# DDS_Module_r2.net
KiCad netlist of a schematic drawn in EAGLE
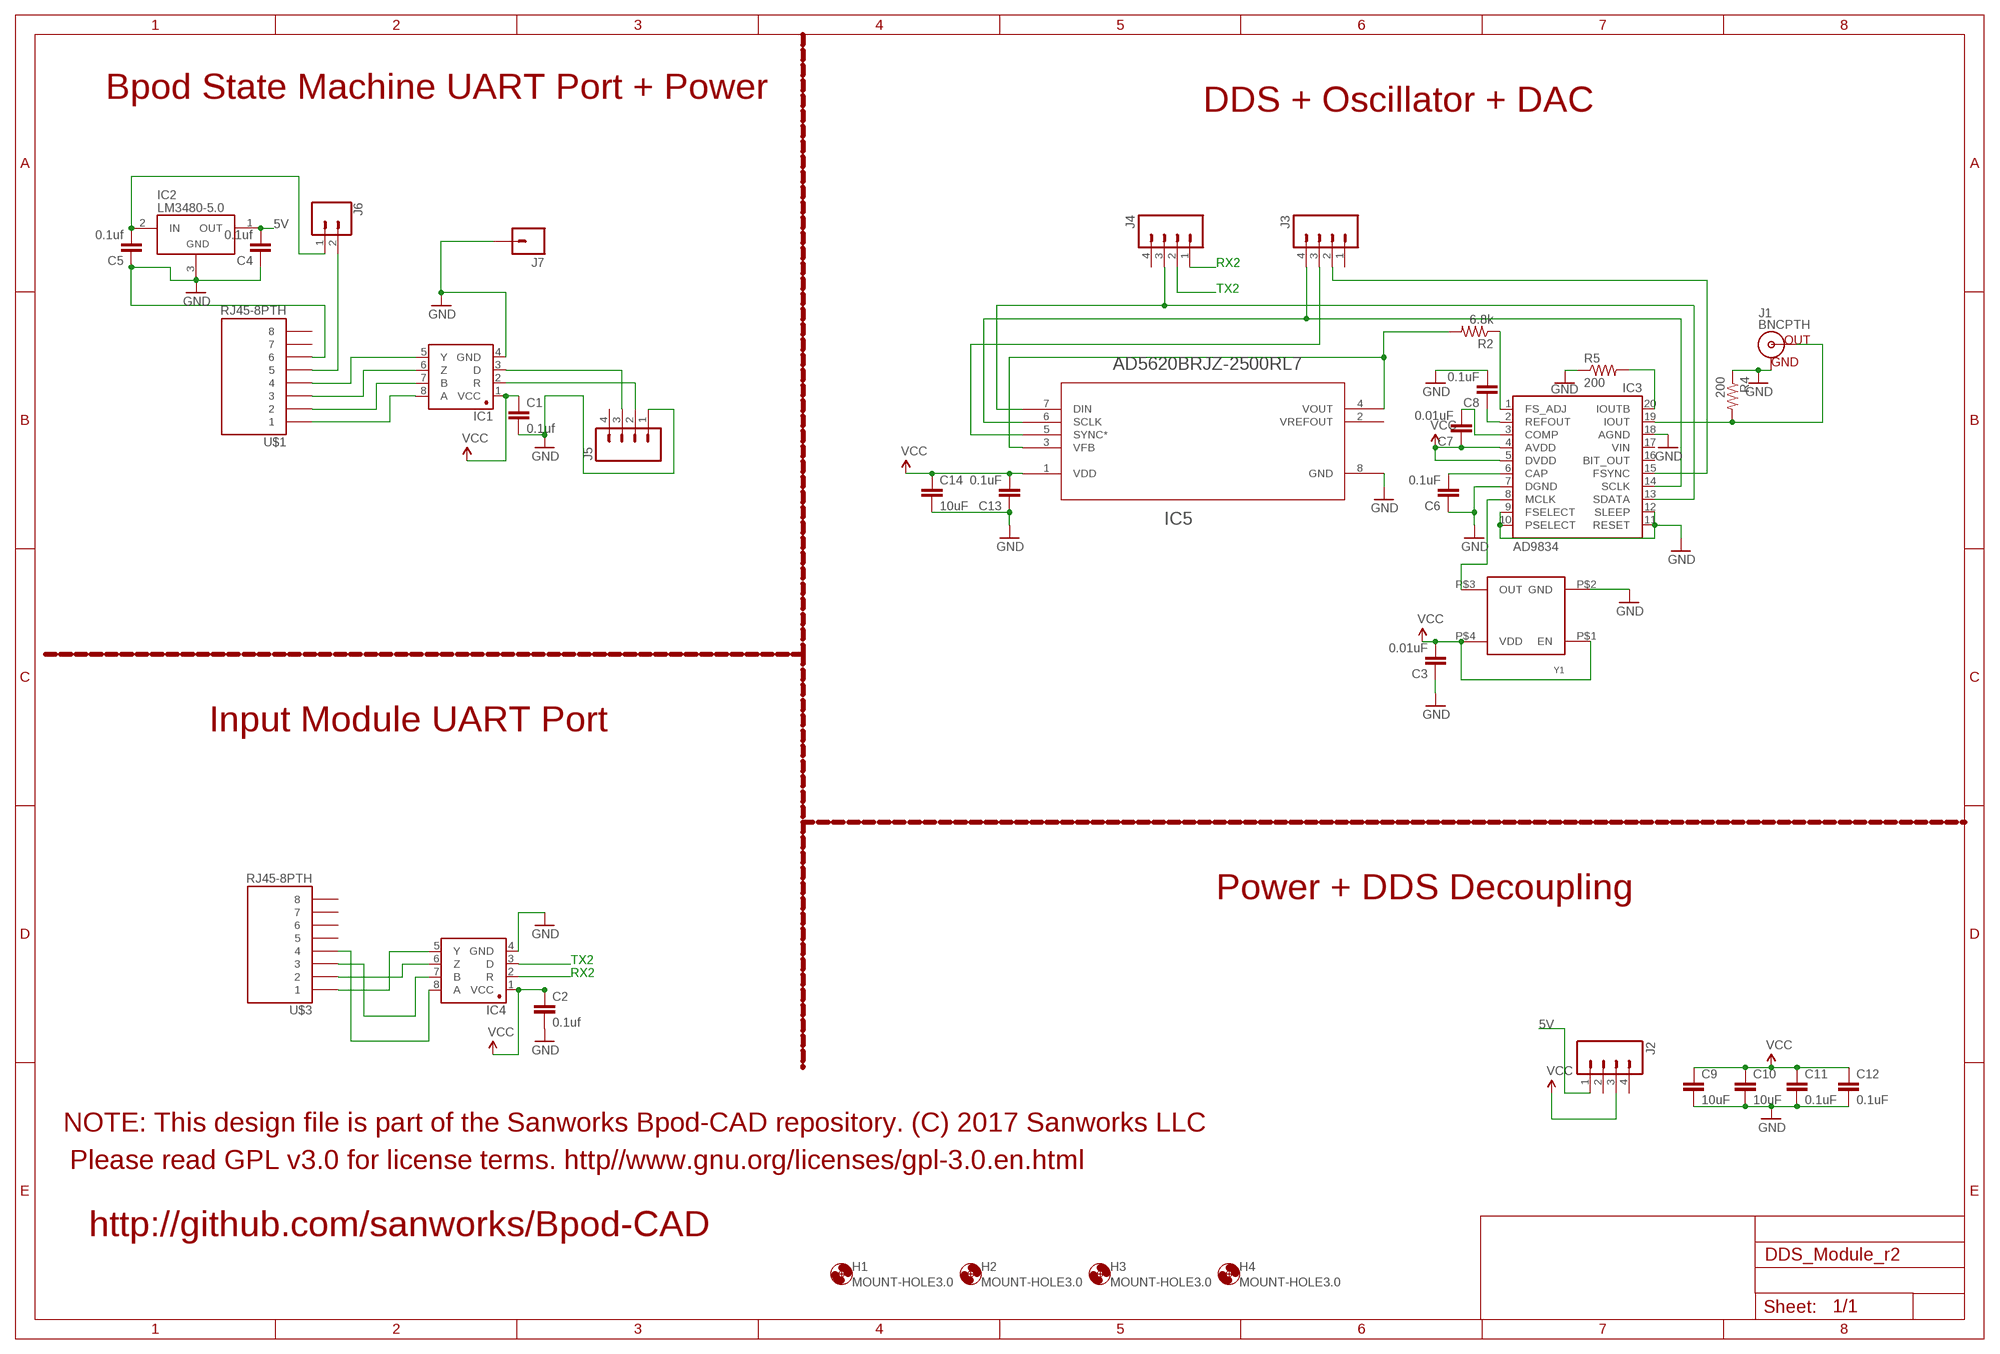
[diagram p0: schematic, sheet 1]

(export (version "E")
  (design (tool "Eeschema 10.0.6"))
  (components
    (comp (ref "C1")
      (value "0.1uf")
      (footprint "eagle-import:1206@1")
      (libsource (lib "eagle-import") (part "CAP1206"))
    )
    (comp (ref "C2")
      (value "0.1uf")
      (footprint "eagle-import:1206@1")
      (libsource (lib "eagle-import") (part "CAP1206"))
    )
    (comp (ref "C3")
      (value "0.01uF")
      (footprint "eagle-import:0805")
      (libsource (lib "eagle-import") (part "10UF-0805-10V-10%"))
    )
    (comp (ref "C4")
      (value "0.1uf")
      (footprint "eagle-import:1206@1")
      (libsource (lib "eagle-import") (part "CAP1206"))
    )
    (comp (ref "C5")
      (value "0.1uf")
      (footprint "eagle-import:1206@1")
      (libsource (lib "eagle-import") (part "CAP1206"))
    )
    (comp (ref "C6")
      (value "0.1uF")
      (footprint "eagle-import:0805")
      (libsource (lib "eagle-import") (part "10UF-0805-10V-10%"))
    )
    (comp (ref "C7")
      (value "0.01uF")
      (footprint "eagle-import:0805")
      (libsource (lib "eagle-import") (part "10UF-0805-10V-10%"))
    )
    (comp (ref "C8")
      (value "0.1uF")
      (footprint "eagle-import:0805")
      (libsource (lib "eagle-import") (part "10UF-0805-10V-10%"))
    )
    (comp (ref "C9")
      (value "10uF")
      (footprint "eagle-import:0805")
      (libsource (lib "eagle-import") (part "10UF-0805-10V-10%"))
    )
    (comp (ref "C10")
      (value "10uF")
      (footprint "eagle-import:0805")
      (libsource (lib "eagle-import") (part "10UF-0805-10V-10%"))
    )
    (comp (ref "C11")
      (value "0.1uF")
      (footprint "eagle-import:0805")
      (libsource (lib "eagle-import") (part "10UF-0805-10V-10%"))
    )
    (comp (ref "C12")
      (value "0.1uF")
      (footprint "eagle-import:0805")
      (libsource (lib "eagle-import") (part "10UF-0805-10V-10%"))
    )
    (comp (ref "C13")
      (value "0.1uF")
      (footprint "eagle-import:0805")
      (libsource (lib "eagle-import") (part "10UF-0805-10V-10%"))
    )
    (comp (ref "C14")
      (value "10uF")
      (footprint "eagle-import:0805")
      (libsource (lib "eagle-import") (part "10UF-0805-10V-10%"))
    )
    (comp (ref "H1")
      (value "MOUNT-HOLE3.0")
      (footprint "eagle-import:3,0")
      (libsource (lib "eagle-import") (part "MOUNT-HOLE3.0"))
    )
    (comp (ref "H2")
      (value "MOUNT-HOLE3.0")
      (footprint "eagle-import:3,0")
      (libsource (lib "eagle-import") (part "MOUNT-HOLE3.0"))
    )
    (comp (ref "H3")
      (value "MOUNT-HOLE3.0")
      (footprint "eagle-import:3,0")
      (libsource (lib "eagle-import") (part "MOUNT-HOLE3.0"))
    )
    (comp (ref "H4")
      (value "MOUNT-HOLE3.0")
      (footprint "eagle-import:3,0")
      (libsource (lib "eagle-import") (part "MOUNT-HOLE3.0"))
    )
    (comp (ref "IC1")
      (value "SN65HVD31DR")
      (footprint "eagle-import:SO08")
      (libsource (lib "eagle-import") (part "SN65HVD31DR"))
    )
    (comp (ref "IC2")
      (value "LM3480-5.0")
      (footprint "eagle-import:SOT-23-3")
      (libsource (lib "eagle-import") (part "LM3480-5.0"))
    )
    (comp (ref "IC3")
      (value "AD9834")
      (footprint "eagle-import:TSSOP20")
      (libsource (lib "eagle-import") (part "AD9834"))
    )
    (comp (ref "IC4")
      (value "SN65HVD31DR")
      (footprint "eagle-import:SO08")
      (libsource (lib "eagle-import") (part "SN65HVD31DR"))
    )
    (comp (ref "IC5")
      (value "AD5620BRJZ-2500RL7")
      (footprint "eagle-import:RJ_8")
      (fields (field (name "MANUFACTURER_PART_NUMBER") "AD5620BRJZ2500RL7"))
      (libsource (lib "eagle-import") (part "AD5620BRJZ-2500RL7"))
    )
    (comp (ref "J1")
      (value "BNCPTH")
      (footprint "eagle-import:BNC")
      (libsource (lib "eagle-import") (part "BNCPTH"))
    )
    (comp (ref "J2")
      (value "M04PTH")
      (footprint "eagle-import:1X04")
      (libsource (lib "eagle-import") (part "M04PTH"))
    )
    (comp (ref "J3")
      (value "M04PTH")
      (footprint "eagle-import:1X04")
      (libsource (lib "eagle-import") (part "M04PTH"))
    )
    (comp (ref "J4")
      (value "M04PTH")
      (footprint "eagle-import:1X04")
      (libsource (lib "eagle-import") (part "M04PTH"))
    )
    (comp (ref "J5")
      (value "M04PTH")
      (footprint "eagle-import:1X04")
      (libsource (lib "eagle-import") (part "M04PTH"))
    )
    (comp (ref "J6")
      (value "CONN_02")
      (footprint "eagle-import:1X02")
      (libsource (lib "eagle-import") (part "CONN_02"))
    )
    (comp (ref "J7")
      (value "M01PTH")
      (footprint "eagle-import:1X01")
      (libsource (lib "eagle-import") (part "M01PTH"))
    )
    (comp (ref "R2")
      (value "6.8k")
      (footprint "eagle-import:R0805")
      (libsource (lib "eagle-import") (part "R-US_R0805"))
    )
    (comp (ref "R4")
      (value "200")
      (footprint "eagle-import:R0805")
      (libsource (lib "eagle-import") (part "R-US_R0805"))
    )
    (comp (ref "R5")
      (value "200")
      (footprint "eagle-import:R0805")
      (libsource (lib "eagle-import") (part "R-US_R0805"))
    )
    (comp (ref "U$1")
      (value "RJ45-8PTH")
      (footprint "eagle-import:RJ45-8")
      (libsource (lib "eagle-import") (part "RJ45-8PTH"))
    )
    (comp (ref "U$3")
      (value "RJ45-8PTH")
      (footprint "eagle-import:RJ45-8")
      (libsource (lib "eagle-import") (part "RJ45-8PTH"))
    )
    (comp (ref "Y1")
      (value "ASE10MHZ")
      (footprint "eagle-import:ASE10MHZ")
      (libsource (lib "eagle-import") (part "ASE10MHZ"))
    )
  )
  (nets
    (net (code "1") (name "/5V") (class "Default")
      (node (ref "C4") (pin "2") (pinfunction "2_2") (pintype "passive"))
      (node (ref "IC2") (pin "1") (pinfunction "OUT_1") (pintype "power_in"))
      (node (ref "J2") (pin "1") (pinfunction "1_1") (pintype "passive"))
    )
    (net (code "2") (name "/RX2") (class "Default")
      (node (ref "IC4") (pin "2") (pinfunction "R_2") (pintype "bidirectional"))
      (node (ref "J4") (pin "1") (pinfunction "1_1") (pintype "passive"))
    )
    (net (code "3") (name "/TX2") (class "Default")
      (node (ref "IC4") (pin "3") (pinfunction "D_3") (pintype "bidirectional"))
      (node (ref "J4") (pin "2") (pinfunction "2_2") (pintype "passive"))
    )
    (net (code "4") (name "GND") (class "Default")
      (node (ref "C1") (pin "2") (pinfunction "2_2") (pintype "passive"))
      (node (ref "C10") (pin "2") (pinfunction "2_2") (pintype "passive"))
      (node (ref "C11") (pin "2") (pinfunction "2_2") (pintype "passive"))
      (node (ref "C12") (pin "2") (pinfunction "2_2") (pintype "passive"))
      (node (ref "C13") (pin "1") (pinfunction "1_1") (pintype "passive"))
      (node (ref "C14") (pin "2") (pinfunction "2_2") (pintype "passive"))
      (node (ref "C2") (pin "2") (pinfunction "2_2") (pintype "passive"))
      (node (ref "C3") (pin "1") (pinfunction "1_1") (pintype "passive"))
      (node (ref "C4") (pin "1") (pinfunction "1_1") (pintype "passive"))
      (node (ref "C5") (pin "1") (pinfunction "1_1") (pintype "passive"))
      (node (ref "C6") (pin "1") (pinfunction "1_1") (pintype "passive"))
      (node (ref "C8") (pin "2") (pinfunction "2_2") (pintype "passive"))
      (node (ref "C9") (pin "2") (pinfunction "2_2") (pintype "passive"))
      (node (ref "IC1") (pin "4") (pinfunction "GND_4") (pintype "bidirectional"))
      (node (ref "IC2") (pin "3") (pinfunction "GND_3") (pintype "power_in"))
      (node (ref "IC3") (pin "10") (pinfunction "PSELECT_10") (pintype "bidirectional"))
      (node (ref "IC3") (pin "11") (pinfunction "RESET_11") (pintype "bidirectional"))
      (node (ref "IC3") (pin "12") (pinfunction "SLEEP_12") (pintype "bidirectional"))
      (node (ref "IC3") (pin "18") (pinfunction "AGND_18") (pintype "bidirectional"))
      (node (ref "IC3") (pin "7") (pinfunction "DGND_7") (pintype "bidirectional"))
      (node (ref "IC3") (pin "9") (pinfunction "FSELECT_9") (pintype "bidirectional"))
      (node (ref "IC4") (pin "4") (pinfunction "GND_4") (pintype "bidirectional"))
      (node (ref "IC5") (pin "8") (pinfunction "GND_8") (pintype "passive"))
      (node (ref "J1") (pin "GND") (pinfunction "GND_GND") (pintype "bidirectional"))
      (node (ref "J5") (pin "1") (pinfunction "1_1") (pintype "passive"))
      (node (ref "J7") (pin "1") (pinfunction "1_1") (pintype "passive"))
      (node (ref "R4") (pin "1") (pinfunction "1_1") (pintype "passive"))
      (node (ref "R5") (pin "1") (pinfunction "1_1") (pintype "passive"))
      (node (ref "U$1") (pin "6") (pinfunction "6_6") (pintype "bidirectional"))
      (node (ref "Y1") (pin "P$2") (pinfunction "GND_P$2") (pintype "bidirectional"))
    )
    (net (code "5") (name "Net-(IC1-A)") (class "Default")
      (node (ref "IC1") (pin "8") (pinfunction "A_8") (pintype "bidirectional"))
      (node (ref "U$1") (pin "1") (pinfunction "1_1") (pintype "bidirectional"))
    )
    (net (code "6") (name "Net-(IC1-B)") (class "Default")
      (node (ref "IC1") (pin "7") (pinfunction "B_7") (pintype "bidirectional"))
      (node (ref "U$1") (pin "2") (pinfunction "2_2") (pintype "bidirectional"))
    )
    (net (code "7") (name "Net-(IC1-D)") (class "Default")
      (node (ref "IC1") (pin "3") (pinfunction "D_3") (pintype "bidirectional"))
      (node (ref "J5") (pin "3") (pinfunction "3_3") (pintype "passive"))
    )
    (net (code "8") (name "Net-(IC1-R)") (class "Default")
      (node (ref "IC1") (pin "2") (pinfunction "R_2") (pintype "bidirectional"))
      (node (ref "J5") (pin "2") (pinfunction "2_2") (pintype "passive"))
    )
    (net (code "9") (name "Net-(IC1-Y)") (class "Default")
      (node (ref "IC1") (pin "5") (pinfunction "Y_5") (pintype "bidirectional"))
      (node (ref "U$1") (pin "4") (pinfunction "4_4") (pintype "bidirectional"))
    )
    (net (code "10") (name "Net-(IC1-Z)") (class "Default")
      (node (ref "IC1") (pin "6") (pinfunction "Z_6") (pintype "bidirectional"))
      (node (ref "U$1") (pin "3") (pinfunction "3_3") (pintype "bidirectional"))
    )
    (net (code "11") (name "Net-(IC2-IN)") (class "Default")
      (node (ref "C5") (pin "2") (pinfunction "2_2") (pintype "passive"))
      (node (ref "IC2") (pin "2") (pinfunction "IN_2") (pintype "power_in"))
      (node (ref "J6") (pin "1") (pinfunction "1_1") (pintype "passive"))
    )
    (net (code "12") (name "Net-(IC3-CAP)") (class "Default")
      (node (ref "C6") (pin "2") (pinfunction "2_2") (pintype "passive"))
      (node (ref "IC3") (pin "6") (pinfunction "CAP_6") (pintype "bidirectional"))
    )
    (net (code "13") (name "Net-(IC3-COMP)") (class "Default")
      (node (ref "C7") (pin "2") (pinfunction "2_2") (pintype "passive"))
      (node (ref "IC3") (pin "3") (pinfunction "COMP_3") (pintype "bidirectional"))
    )
    (net (code "14") (name "Net-(IC3-FSYNC)") (class "Default")
      (node (ref "IC3") (pin "15") (pinfunction "FSYNC_15") (pintype "bidirectional"))
      (node (ref "J3") (pin "2") (pinfunction "2_2") (pintype "passive"))
    )
    (net (code "15") (name "Net-(IC3-FS_ADJ)") (class "Default")
      (node (ref "IC3") (pin "1") (pinfunction "FS_ADJ_1") (pintype "bidirectional"))
      (node (ref "R2") (pin "1") (pinfunction "1_1") (pintype "passive"))
    )
    (net (code "16") (name "Net-(IC3-IOUT)") (class "Default")
      (node (ref "IC3") (pin "19") (pinfunction "IOUT_19") (pintype "bidirectional"))
      (node (ref "J1") (pin "S") (pinfunction "OUT_S") (pintype "bidirectional"))
      (node (ref "R4") (pin "2") (pinfunction "2_2") (pintype "passive"))
    )
    (net (code "17") (name "Net-(IC3-IOUTB)") (class "Default")
      (node (ref "IC3") (pin "20") (pinfunction "IOUTB_20") (pintype "bidirectional"))
      (node (ref "R5") (pin "2") (pinfunction "2_2") (pintype "passive"))
    )
    (net (code "18") (name "Net-(IC3-MCLK)") (class "Default")
      (node (ref "IC3") (pin "8") (pinfunction "MCLK_8") (pintype "bidirectional"))
      (node (ref "Y1") (pin "P$3") (pinfunction "OUT_P$3") (pintype "bidirectional"))
    )
    (net (code "19") (name "Net-(IC3-REFOUT)") (class "Default")
      (node (ref "C8") (pin "1") (pinfunction "1_1") (pintype "passive"))
      (node (ref "IC3") (pin "2") (pinfunction "REFOUT_2") (pintype "bidirectional"))
    )
    (net (code "20") (name "Net-(IC3-SCLK)") (class "Default")
      (node (ref "IC3") (pin "14") (pinfunction "SCLK_14") (pintype "bidirectional"))
      (node (ref "IC5") (pin "6") (pinfunction "SCLK_6") (pintype "passive"))
      (node (ref "J3") (pin "4") (pinfunction "4_4") (pintype "passive"))
    )
    (net (code "21") (name "Net-(IC3-SDATA)") (class "Default")
      (node (ref "IC3") (pin "13") (pinfunction "SDATA_13") (pintype "bidirectional"))
      (node (ref "IC5") (pin "7") (pinfunction "DIN_7") (pintype "passive"))
      (node (ref "J4") (pin "3") (pinfunction "3_3") (pintype "passive"))
    )
    (net (code "22") (name "Net-(IC4-A)") (class "Default")
      (node (ref "IC4") (pin "8") (pinfunction "A_8") (pintype "bidirectional"))
      (node (ref "U$3") (pin "4") (pinfunction "4_4") (pintype "bidirectional"))
    )
    (net (code "23") (name "Net-(IC4-B)") (class "Default")
      (node (ref "IC4") (pin "7") (pinfunction "B_7") (pintype "bidirectional"))
      (node (ref "U$3") (pin "3") (pinfunction "3_3") (pintype "bidirectional"))
    )
    (net (code "24") (name "Net-(IC4-Y)") (class "Default")
      (node (ref "IC4") (pin "5") (pinfunction "Y_5") (pintype "bidirectional"))
      (node (ref "U$3") (pin "1") (pinfunction "1_1") (pintype "bidirectional"))
    )
    (net (code "25") (name "Net-(IC4-Z)") (class "Default")
      (node (ref "IC4") (pin "6") (pinfunction "Z_6") (pintype "bidirectional"))
      (node (ref "U$3") (pin "2") (pinfunction "2_2") (pintype "bidirectional"))
    )
    (net (code "26") (name "Net-(IC5-SYNC*)") (class "Default")
      (node (ref "IC5") (pin "5") (pinfunction "SYNC*_5") (pintype "passive"))
      (node (ref "J3") (pin "3") (pinfunction "3_3") (pintype "passive"))
    )
    (net (code "27") (name "Net-(IC5-VFB)") (class "Default")
      (node (ref "IC5") (pin "3") (pinfunction "VFB_3") (pintype "passive"))
      (node (ref "IC5") (pin "4") (pinfunction "VOUT_4") (pintype "passive"))
      (node (ref "R2") (pin "2") (pinfunction "2_2") (pintype "passive"))
    )
    (net (code "28") (name "Net-(J6-Pad2)") (class "Default")
      (node (ref "J6") (pin "2") (pinfunction "2_2") (pintype "passive"))
      (node (ref "U$1") (pin "5") (pinfunction "5_5") (pintype "bidirectional"))
    )
    (net (code "29") (name "VCC") (class "Default")
      (node (ref "C1") (pin "1") (pinfunction "1_1") (pintype "passive"))
      (node (ref "C10") (pin "1") (pinfunction "1_1") (pintype "passive"))
      (node (ref "C11") (pin "1") (pinfunction "1_1") (pintype "passive"))
      (node (ref "C12") (pin "1") (pinfunction "1_1") (pintype "passive"))
      (node (ref "C13") (pin "2") (pinfunction "2_2") (pintype "passive"))
      (node (ref "C14") (pin "1") (pinfunction "1_1") (pintype "passive"))
      (node (ref "C2") (pin "1") (pinfunction "1_1") (pintype "passive"))
      (node (ref "C3") (pin "2") (pinfunction "2_2") (pintype "passive"))
      (node (ref "C7") (pin "1") (pinfunction "1_1") (pintype "passive"))
      (node (ref "C9") (pin "1") (pinfunction "1_1") (pintype "passive"))
      (node (ref "IC1") (pin "1") (pinfunction "VCC_1") (pintype "bidirectional"))
      (node (ref "IC3") (pin "4") (pinfunction "AVDD_4") (pintype "bidirectional"))
      (node (ref "IC3") (pin "5") (pinfunction "DVDD_5") (pintype "bidirectional"))
      (node (ref "IC4") (pin "1") (pinfunction "VCC_1") (pintype "bidirectional"))
      (node (ref "IC5") (pin "1") (pinfunction "VDD_1") (pintype "power_in"))
      (node (ref "J2") (pin "3") (pinfunction "3_3") (pintype "passive"))
      (node (ref "Y1") (pin "P$1") (pinfunction "EN_P$1") (pintype "bidirectional"))
      (node (ref "Y1") (pin "P$4") (pinfunction "VDD_P$4") (pintype "bidirectional"))
    )
    (net (code "30") (name "unconnected-(IC3-BIT_OUT-Pad16)") (class "Default")
      (node (ref "IC3") (pin "16") (pinfunction "BIT_OUT_16") (pintype "bidirectional"))
    )
    (net (code "31") (name "unconnected-(IC3-VIN-Pad17)") (class "Default")
      (node (ref "IC3") (pin "17") (pinfunction "VIN_17") (pintype "bidirectional"))
    )
    (net (code "32") (name "unconnected-(IC5-VREFOUT-Pad2)") (class "Default")
      (node (ref "IC5") (pin "2") (pinfunction "VREFOUT_2") (pintype "passive"))
    )
    (net (code "33") (name "unconnected-(J2-Pad2)") (class "Default")
      (node (ref "J2") (pin "2") (pinfunction "2_2") (pintype "passive"))
    )
    (net (code "34") (name "unconnected-(J2-Pad4)") (class "Default")
      (node (ref "J2") (pin "4") (pinfunction "4_4") (pintype "passive"))
    )
    (net (code "35") (name "unconnected-(J3-Pad1)") (class "Default")
      (node (ref "J3") (pin "1") (pinfunction "1_1") (pintype "passive"))
    )
    (net (code "36") (name "unconnected-(J4-Pad4)") (class "Default")
      (node (ref "J4") (pin "4") (pinfunction "4_4") (pintype "passive"))
    )
    (net (code "37") (name "unconnected-(J5-Pad4)") (class "Default")
      (node (ref "J5") (pin "4") (pinfunction "4_4") (pintype "passive"))
    )
    (net (code "38") (name "unconnected-(U$1-Pad7)") (class "Default")
      (node (ref "U$1") (pin "7") (pinfunction "7_7") (pintype "bidirectional"))
    )
    (net (code "39") (name "unconnected-(U$1-Pad8)") (class "Default")
      (node (ref "U$1") (pin "8") (pinfunction "8_8") (pintype "bidirectional"))
    )
    (net (code "40") (name "unconnected-(U$3-Pad5)") (class "Default")
      (node (ref "U$3") (pin "5") (pinfunction "5_5") (pintype "bidirectional"))
    )
    (net (code "41") (name "unconnected-(U$3-Pad6)") (class "Default")
      (node (ref "U$3") (pin "6") (pinfunction "6_6") (pintype "bidirectional"))
    )
    (net (code "42") (name "unconnected-(U$3-Pad7)") (class "Default")
      (node (ref "U$3") (pin "7") (pinfunction "7_7") (pintype "bidirectional"))
    )
    (net (code "43") (name "unconnected-(U$3-Pad8)") (class "Default")
      (node (ref "U$3") (pin "8") (pinfunction "8_8") (pintype "bidirectional"))
    )
  )
)
